# attinier84-2digit-shield-mk-2_1.net
KiCad netlist of a schematic drawn in EAGLE
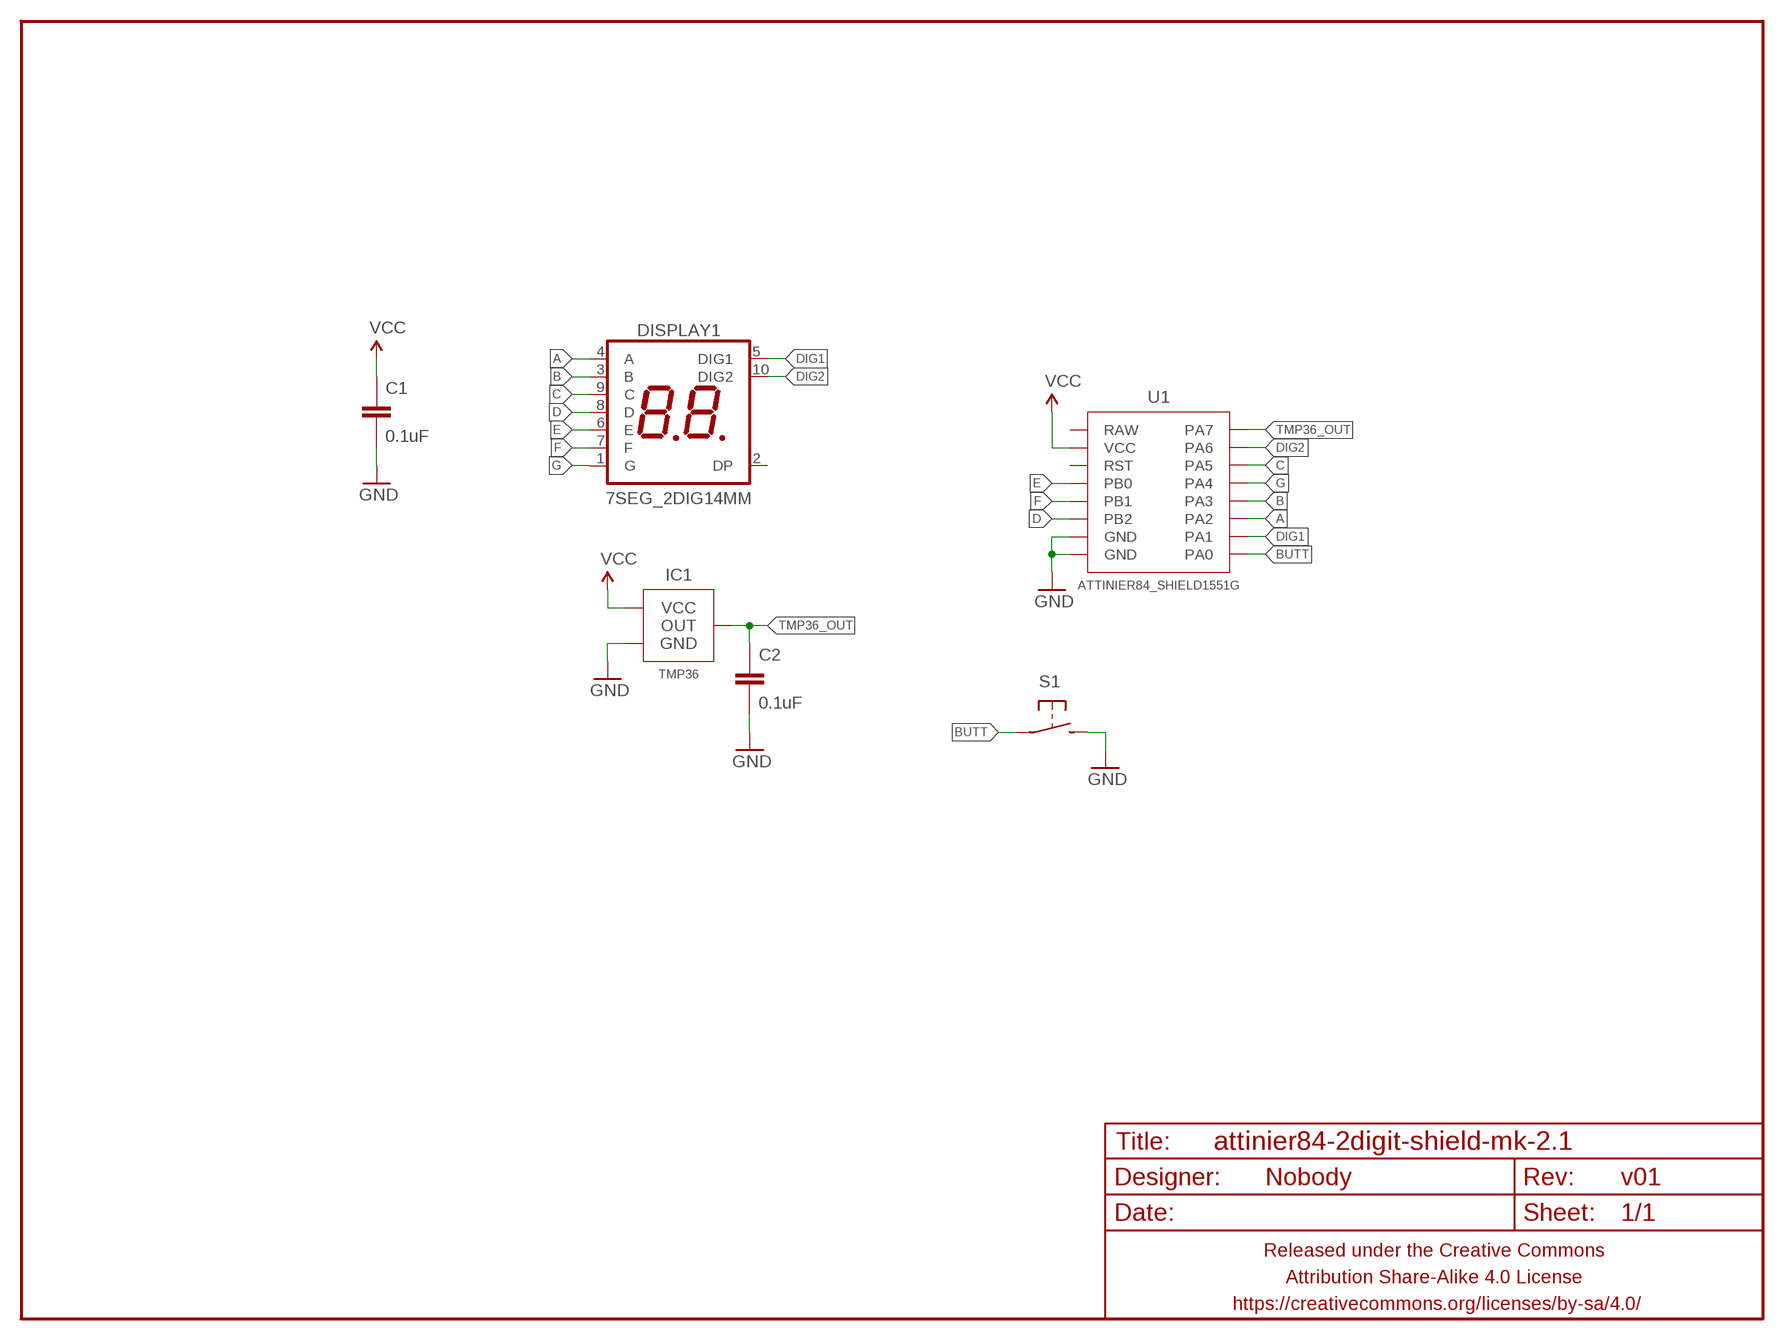
[diagram p0: schematic, sheet 1]

(export (version "E")
  (design (tool "Eeschema 10.0.6"))
  (components
    (comp (ref "C1")
      (value "0.1uF")
      (footprint "eagle-import:C025-024X044")
      (libsource (lib "eagle-import") (part "CAPACITOR-CERAMIC025-024X044"))
    )
    (comp (ref "C2")
      (value "0.1uF")
      (footprint "eagle-import:C025-024X044")
      (libsource (lib "eagle-import") (part "CAPACITOR-CERAMIC025-024X044"))
    )
    (comp (ref "DISPLAY1")
      (value "7SEG_2DIG14MM")
      (footprint "eagle-import:7SEG_2DIG_14MM")
      (libsource (lib "eagle-import") (part "7SEG_2DIG14MM"))
    )
    (comp (ref "FRAME1")
      (value "FRAME-LETTERNO_PACKAGE")
      (footprint "eagle-import:DUMMY")
      (fields (field (name "DESIGNER") "Nobody"))
      (libsource (lib "eagle-import") (part "FRAME-LETTERNO_PACKAGE"))
    )
    (comp (ref "IC1")
      (value "TMP36")
      (footprint "eagle-import:TO-92-AMMO")
      (libsource (lib "eagle-import") (part "TMP36TO-92"))
    )
    (comp (ref "S1")
      (value "SPST-NO-TACT3MM-PTH-SMALL-PADS")
      (footprint "eagle-import:DTS-3-SMALL-PADS")
      (libsource (lib "eagle-import") (part "SPST-NO-TACT3MM-PTH-SMALL-PADS"))
    )
    (comp (ref "U1")
      (value "ATTINIER84_SHIELD1551G")
      (footprint "eagle-import:ATTINIER84_SHIELD2")
      (libsource (lib "eagle-import") (part "ATTINIER84_SHIELD1551G"))
    )
  )
  (nets
    (net (code "1") (name "A") (class "Default")
      (node (ref "DISPLAY1") (pin "4") (pinfunction "A_4") (pintype "passive"))
      (node (ref "U1") (pin "PA2") (pinfunction "PA2_PA2") (pintype "bidirectional"))
    )
    (net (code "2") (name "B") (class "Default")
      (node (ref "DISPLAY1") (pin "3") (pinfunction "B_3") (pintype "passive"))
      (node (ref "U1") (pin "PA3") (pinfunction "PA3_PA3") (pintype "bidirectional"))
    )
    (net (code "3") (name "BUTT") (class "Default")
      (node (ref "S1") (pin "1") (pinfunction "1_1") (pintype "passive"))
      (node (ref "U1") (pin "PA0") (pinfunction "PA0_PA0") (pintype "bidirectional"))
    )
    (net (code "4") (name "C") (class "Default")
      (node (ref "DISPLAY1") (pin "9") (pinfunction "C_9") (pintype "passive"))
      (node (ref "U1") (pin "PA5") (pinfunction "PA5_PA5") (pintype "bidirectional"))
    )
    (net (code "5") (name "D") (class "Default")
      (node (ref "DISPLAY1") (pin "8") (pinfunction "D_8") (pintype "passive"))
      (node (ref "U1") (pin "PB2") (pinfunction "PB2_PB2") (pintype "bidirectional"))
    )
    (net (code "6") (name "DIG1") (class "Default")
      (node (ref "DISPLAY1") (pin "5") (pinfunction "DIG1_5") (pintype "passive"))
      (node (ref "U1") (pin "PA1") (pinfunction "PA1_PA1") (pintype "bidirectional"))
    )
    (net (code "7") (name "DIG2") (class "Default")
      (node (ref "DISPLAY1") (pin "10") (pinfunction "DIG2_10") (pintype "passive"))
      (node (ref "U1") (pin "PA6") (pinfunction "PA6_PA6") (pintype "bidirectional"))
    )
    (net (code "8") (name "E") (class "Default")
      (node (ref "DISPLAY1") (pin "6") (pinfunction "E_6") (pintype "passive"))
      (node (ref "U1") (pin "PB0") (pinfunction "PB0_PB0") (pintype "bidirectional"))
    )
    (net (code "9") (name "F") (class "Default")
      (node (ref "DISPLAY1") (pin "7") (pinfunction "F_7") (pintype "passive"))
      (node (ref "U1") (pin "PB1") (pinfunction "PB1_PB1") (pintype "bidirectional"))
    )
    (net (code "10") (name "G") (class "Default")
      (node (ref "DISPLAY1") (pin "1") (pinfunction "G_1") (pintype "passive"))
      (node (ref "U1") (pin "PA4") (pinfunction "PA4_PA4") (pintype "bidirectional"))
    )
    (net (code "11") (name "GND") (class "Default")
      (node (ref "C1") (pin "2") (pinfunction "2_2") (pintype "passive"))
      (node (ref "C2") (pin "2") (pinfunction "2_2") (pintype "passive"))
      (node (ref "IC1") (pin "3") (pinfunction "GND_3") (pintype "bidirectional"))
      (node (ref "S1") (pin "2") (pinfunction "2_2") (pintype "passive"))
      (node (ref "U1") (pin "GND@1") (pinfunction "GND_GND@1") (pintype "bidirectional"))
      (node (ref "U1") (pin "GND@2") (pinfunction "GND_GND@2") (pintype "bidirectional"))
    )
    (net (code "12") (name "TMP36_OUT") (class "Default")
      (node (ref "C2") (pin "1") (pinfunction "1_1") (pintype "passive"))
      (node (ref "IC1") (pin "2") (pinfunction "OUT_2") (pintype "bidirectional"))
      (node (ref "U1") (pin "PA7") (pinfunction "PA7_PA7") (pintype "bidirectional"))
    )
    (net (code "13") (name "VCC") (class "Default")
      (node (ref "C1") (pin "1") (pinfunction "1_1") (pintype "passive"))
      (node (ref "IC1") (pin "1") (pinfunction "VCC_1") (pintype "bidirectional"))
      (node (ref "U1") (pin "VCC") (pinfunction "VCC_VCC") (pintype "bidirectional"))
    )
    (net (code "14") (name "unconnected-(DISPLAY1-DP-Pad2)") (class "Default")
      (node (ref "DISPLAY1") (pin "2") (pinfunction "DP_2") (pintype "passive"))
    )
    (net (code "15") (name "unconnected-(U1-PadRAW)") (class "Default")
      (node (ref "U1") (pin "RAW") (pinfunction "RAW_RAW") (pintype "bidirectional"))
    )
    (net (code "16") (name "unconnected-(U1-PadRST)") (class "Default")
      (node (ref "U1") (pin "RST") (pinfunction "RST_RST") (pintype "bidirectional"))
    )
  )
)
